# Rectifier-SinglePhase-FullControlled-TCA.net
KiCad netlist of a schematic drawn in Altium Designer
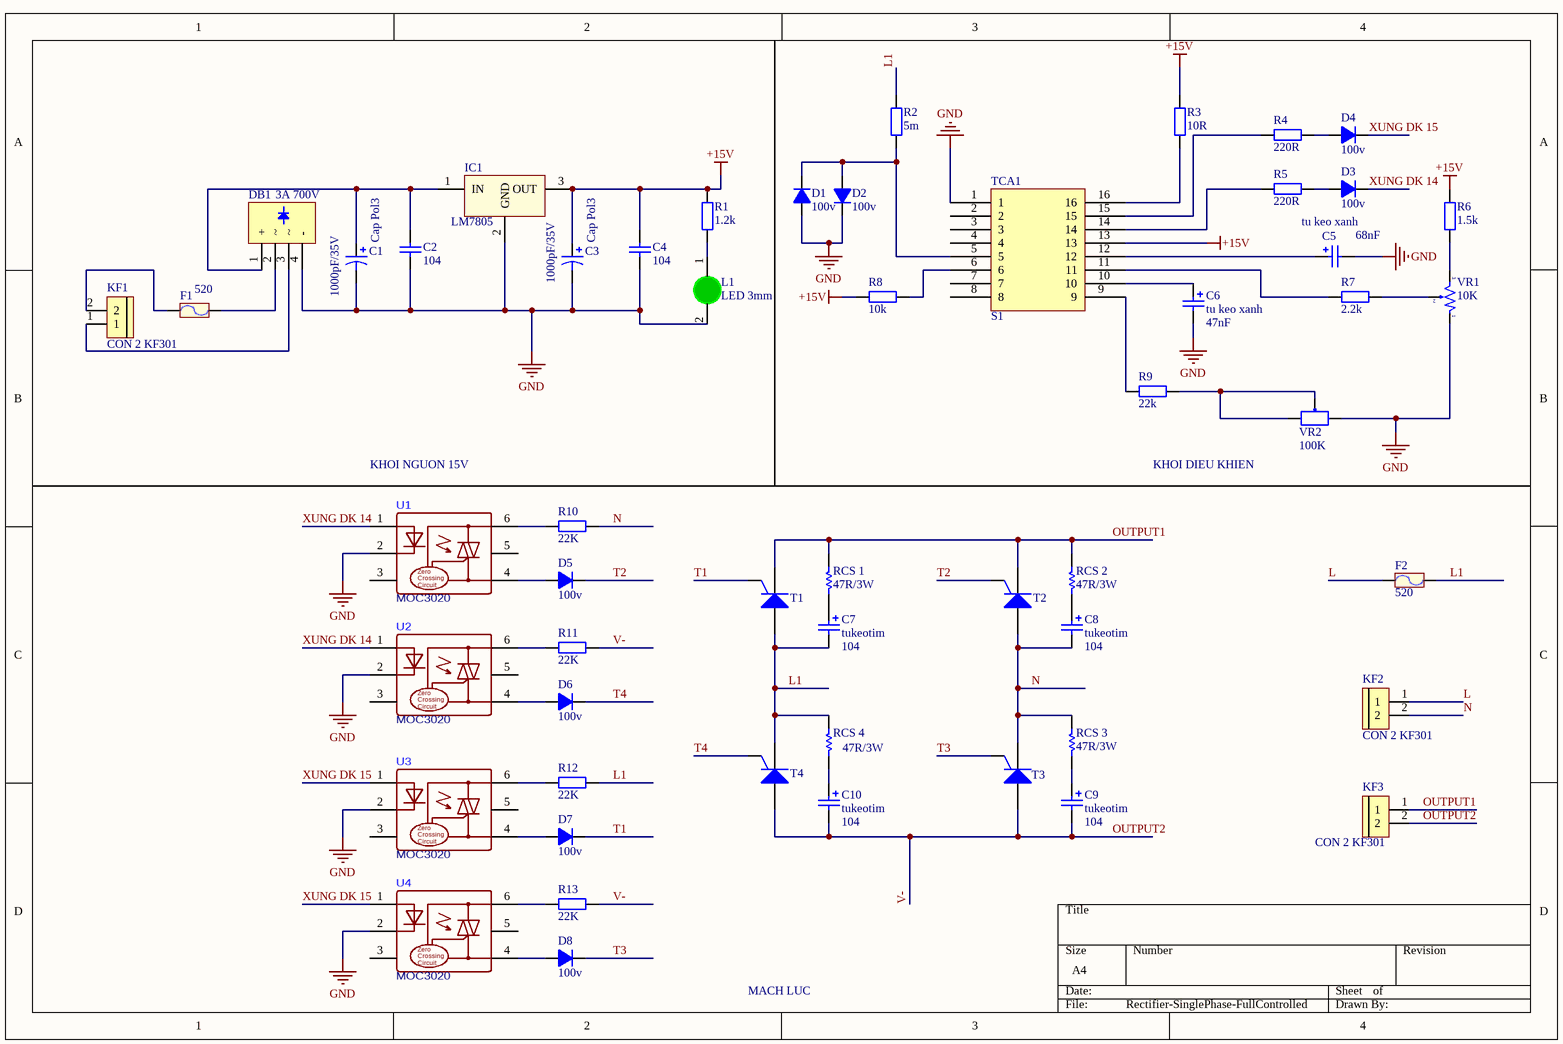
[diagram p0: Rectifier-SinglePhase-FullControlled-TCA785.SchDoc]

(export (version "E")
  (design (tool "Eeschema 10.0.6"))
  (components
    (comp (ref "C1")
      (value "Cap Pol3")
      (footprint "CP2/5")
      (description "Polarized Capacitor (Surface Mount)")
      (fields (field (name "ALTIUM_VALUE") "1000pF/35V") (field (name "PUBLISHER") "Altium Limited"))
      (libsource (lib "syhaunguyen") (part "Cap Pol3_3"))
    )
    (comp (ref "C2")
      (value "104")
      (footprint "tu gom")
      (description "Cắm")
      (libsource (lib "Tu dien") (part "Tu gom 104 50V"))
    )
    (comp (ref "C3")
      (value "Cap Pol3")
      (footprint "CP2/5")
      (description "Polarized Capacitor (Surface Mount)")
      (fields (field (name "ALTIUM_VALUE") "1000pF/35V") (field (name "PUBLISHER") "Altium Limited"))
      (libsource (lib "syhaunguyen") (part "Cap Pol3_3"))
    )
    (comp (ref "C4")
      (value "104")
      (footprint "tu gom")
      (description "Cắm")
      (libsource (lib "Tu dien") (part "Tu gom 104 50V"))
    )
    (comp (ref "C5")
      (value "tu keo xanh")
      (footprint "tu keo xanh")
      (description "Polarized Capacitor (Surface Mount)")
      (fields (field (name "ALTIUM_VALUE") "68nF") (field (name "PUBLISHER") "Altium Limited"))
      (libsource (lib "syhaunguyen") (part "tu keo xanh"))
    )
    (comp (ref "C6")
      (value "tu keo xanh")
      (footprint "tu keo xanh")
      (description "Polarized Capacitor (Surface Mount)")
      (fields (field (name "ALTIUM_VALUE") "47nF") (field (name "PUBLISHER") "Altium Limited"))
      (libsource (lib "syhaunguyen") (part "tu keo xanh"))
    )
    (comp (ref "C7")
      (value "tukeotim")
      (footprint "tu keo")
      (description "Polarized Capacitor (Surface Mount)")
      (fields (field (name "ALTIUM_VALUE") "104") (field (name "PUBLISHER") "Altium Limited"))
      (libsource (lib "syhaunguyen") (part "tu keo tim"))
    )
    (comp (ref "C8")
      (value "tukeotim")
      (footprint "tu keo")
      (description "Polarized Capacitor (Surface Mount)")
      (fields (field (name "ALTIUM_VALUE") "104") (field (name "PUBLISHER") "Altium Limited"))
      (libsource (lib "syhaunguyen") (part "tu keo tim"))
    )
    (comp (ref "C9")
      (value "tukeotim")
      (footprint "tu keo")
      (description "Polarized Capacitor (Surface Mount)")
      (fields (field (name "ALTIUM_VALUE") "104") (field (name "PUBLISHER") "Altium Limited"))
      (libsource (lib "syhaunguyen") (part "tu keo tim"))
    )
    (comp (ref "C10")
      (value "tukeotim")
      (footprint "tu keo")
      (description "Polarized Capacitor (Surface Mount)")
      (fields (field (name "ALTIUM_VALUE") "104") (field (name "PUBLISHER") "Altium Limited"))
      (libsource (lib "syhaunguyen") (part "tu keo tim"))
    )
    (comp (ref "D1")
      (value "100v")
      (footprint "DIODE 1A")
      (description "Cắm")
      (libsource (lib "Altium_Lib_by_KhueNguyenCreator") (part "Diode 1N4007"))
    )
    (comp (ref "D2")
      (value "100v")
      (footprint "DIODE 1A")
      (description "Cắm")
      (libsource (lib "Altium_Lib_by_KhueNguyenCreator") (part "Diode 1N4007"))
    )
    (comp (ref "D3")
      (value "100v")
      (footprint "DIODE 1A")
      (description "Cắm")
      (libsource (lib "Altium_Lib_by_KhueNguyenCreator") (part "Diode 1N4007"))
    )
    (comp (ref "D4")
      (value "100v")
      (footprint "DIODE 1A")
      (description "Cắm")
      (libsource (lib "Altium_Lib_by_KhueNguyenCreator") (part "Diode 1N4007"))
    )
    (comp (ref "D5")
      (value "100v")
      (footprint "DIODE 1A")
      (description "Cắm")
      (libsource (lib "Altium_Lib_by_KhueNguyenCreator") (part "Diode 1N4007"))
    )
    (comp (ref "D6")
      (value "100v")
      (footprint "DIODE 1A")
      (description "Cắm")
      (libsource (lib "Altium_Lib_by_KhueNguyenCreator") (part "Diode 1N4007"))
    )
    (comp (ref "D7")
      (value "100v")
      (footprint "DIODE 1A")
      (description "Cắm")
      (libsource (lib "Altium_Lib_by_KhueNguyenCreator") (part "Diode 1N4007"))
    )
    (comp (ref "D8")
      (value "100v")
      (footprint "DIODE 1A")
      (description "Cắm")
      (libsource (lib "Altium_Lib_by_KhueNguyenCreator") (part "Diode 1N4007"))
    )
    (comp (ref "DB1")
      (value "3A 700V")
      (footprint "DIODE CAU 2A 3A CAM")
      (description "Cắm")
      (libsource (lib "Altium_Lib_by_KhueNguyenCreator") (part "Diode CAU 3A"))
    )
    (comp (ref "F1")
      (value "520")
      (footprint "De Cau Chi 520 630")
      (description "5x20mm")
      (libsource (lib "Altium_Lib_by_KhueNguyenCreator") (part "De Cau Chi 520 630"))
    )
    (comp (ref "F2")
      (value "520")
      (footprint "De Cau Chi 520 630")
      (description "5x20mm")
      (libsource (lib "Altium_Lib_by_KhueNguyenCreator") (part "De Cau Chi 520 630"))
    )
    (comp (ref "IC1")
      (value "LM7805")
      (footprint "QTO-220")
      (description "On ap +, from + 5 to + 24VDC")
      (libsource (lib "Free Documents") (part "LM78xx"))
    )
    (comp (ref "KF1")
      (value "CON 2 KF301")
      (footprint "Con 2 KF301 5.08")
      (description "Cắm")
      (libsource (lib "") (part "CON 2 KF301_1"))
    )
    (comp (ref "KF2")
      (value "CON 2 KF301")
      (footprint "Con 2 KF301 5.08")
      (description "Cắm")
      (libsource (lib "Altium_Lib_by_KhueNguyenCreator") (part "CON 2 KF301"))
    )
    (comp (ref "KF3")
      (value "CON 2 KF301")
      (footprint "Con 2 KF301 5.08")
      (description "Cắm")
      (libsource (lib "Altium_Lib_by_KhueNguyenCreator") (part "CON 2 KF301"))
    )
    (comp (ref "L1")
      (value "LED 3mm")
      (footprint "LED-3MM-GREEN")
      (description "Cắm")
      (libsource (lib "Altium_Lib_by_KhueNguyenCreator") (part "LED 3mm Xanh La"))
    )
    (comp (ref "R1")
      (value "1.2k")
      (footprint "tro vach 1/4w")
      (description "Cắm")
      (libsource (lib "Altium_Lib_by_KhueNguyenCreator") (part "Tro Vach 1/4W 5% 1.2R"))
    )
    (comp (ref "R2")
      (value "5m")
      (footprint "tro vach 1/4w")
      (description "Cắm")
      (libsource (lib "Altium_Lib_by_KhueNguyenCreator") (part "Tro Vach 1/4W 5% 1.2R"))
    )
    (comp (ref "R3")
      (value "10R")
      (footprint "tro vach 1/4w")
      (description "Cắm")
      (libsource (lib "Altium_Lib_by_KhueNguyenCreator") (part "Tro Vach 1/4W 5% 1.2R"))
    )
    (comp (ref "R4")
      (value "220R")
      (footprint "tro vach 1/4w")
      (description "Cắm")
      (libsource (lib "Altium_Lib_by_KhueNguyenCreator") (part "Tro Vach 1/4W 5% 1.2R"))
    )
    (comp (ref "R5")
      (value "220R")
      (footprint "tro vach 1/4w")
      (description "Cắm")
      (libsource (lib "Altium_Lib_by_KhueNguyenCreator") (part "Tro Vach 1/4W 5% 1.2R"))
    )
    (comp (ref "R6")
      (value "1.5k")
      (footprint "tro vach 1/4w")
      (description "Cắm")
      (libsource (lib "Altium_Lib_by_KhueNguyenCreator") (part "Tro Vach 1/4W 5% 1.2R"))
    )
    (comp (ref "R7")
      (value "2.2k")
      (footprint "tro vach 1/4w")
      (description "Cắm")
      (libsource (lib "Altium_Lib_by_KhueNguyenCreator") (part "Tro Vach 1/4W 5% 1.2R"))
    )
    (comp (ref "R8")
      (value "10k")
      (footprint "tro vach 1/4w")
      (description "Cắm")
      (libsource (lib "Altium_Lib_by_KhueNguyenCreator") (part "Tro Vach 1/4W 5% 1.2R"))
    )
    (comp (ref "R9")
      (value "22k")
      (footprint "tro vach 1/4w")
      (description "Cắm")
      (libsource (lib "Altium_Lib_by_KhueNguyenCreator") (part "Tro Vach 1/4W 5% 1.2R"))
    )
    (comp (ref "R10")
      (value "22K")
      (footprint "tro vach 1/4w")
      (description "Cắm")
      (libsource (lib "Altium_Lib_by_KhueNguyenCreator") (part "Tro Vach 1/4W 5% 1.2R"))
    )
    (comp (ref "R11")
      (value "22K")
      (footprint "tro vach 1/4w")
      (description "Cắm")
      (libsource (lib "Altium_Lib_by_KhueNguyenCreator") (part "Tro Vach 1/4W 5% 1.2R"))
    )
    (comp (ref "R12")
      (value "22K")
      (footprint "tro vach 1/4w")
      (description "Cắm")
      (libsource (lib "Altium_Lib_by_KhueNguyenCreator") (part "Tro Vach 1/4W 5% 1.2R"))
    )
    (comp (ref "R13")
      (value "22K")
      (footprint "tro vach 1/4w")
      (description "Cắm")
      (libsource (lib "Altium_Lib_by_KhueNguyenCreator") (part "Tro Vach 1/4W 5% 1.2R"))
    )
    (comp (ref "RCS 1")
      (value "47R/3W")
      (footprint "TRO CONG SUAT")
      (description "Resistor")
      (fields
        (field (name "MANUFACTURER") "Generic Components")
        (field (name "Comment") "Res")
        (field (name "PUBLISHER") "Altium Hobart Technology Centre")
      )
      (libsource (lib "syhaunguyen") (part "TRO CONG SUAT"))
    )
    (comp (ref "RCS 2")
      (value "47R/3W")
      (footprint "TRO CONG SUAT")
      (description "Resistor")
      (fields
        (field (name "MANUFACTURER") "Generic Components")
        (field (name "Comment") "Res")
        (field (name "PUBLISHER") "Altium Hobart Technology Centre")
      )
      (libsource (lib "syhaunguyen") (part "TRO CONG SUAT"))
    )
    (comp (ref "RCS 3")
      (value "47R/3W")
      (footprint "TRO CONG SUAT")
      (description "Resistor")
      (fields
        (field (name "MANUFACTURER") "Generic Components")
        (field (name "Comment") "Res")
        (field (name "PUBLISHER") "Altium Hobart Technology Centre")
      )
      (libsource (lib "syhaunguyen") (part "TRO CONG SUAT"))
    )
    (comp (ref "RCS 4")
      (value "47R/3W")
      (footprint "TRO CONG SUAT")
      (description "Resistor")
      (fields
        (field (name "MANUFACTURER") "Generic Components")
        (field (name "Comment") "Res")
        (field (name "PUBLISHER") "Altium Hobart Technology Centre")
      )
      (libsource (lib "syhaunguyen") (part "TRO CONG SUAT"))
    )
    (comp (ref "T1")
      (value "SCR Thyristror")
      (footprint "scr")
      (libsource (lib "syhaunguyen") (part "SCR_1"))
    )
    (comp (ref "T2")
      (value "SCR Thyristror")
      (footprint "scr")
      (libsource (lib "syhaunguyen") (part "SCR_1"))
    )
    (comp (ref "T3")
      (value "SCR Thyristror")
      (footprint "scr")
      (libsource (lib "syhaunguyen") (part "SCR_1"))
    )
    (comp (ref "T4")
      (value "SCR Thyristror")
      (footprint "scr")
      (libsource (lib "syhaunguyen") (part "SCR_1"))
    )
    (comp (ref "TCA1")
      (value "S1")
      (footprint "DIP16/W0.3 - duplicate")
      (libsource (lib "syhaunguyen") (part "TCA 785"))
    )
    (comp (ref "U1")
      (value "MOC3020")
      (footprint "DIP6")
      (libsource (lib "Altium_Lib_by_KhueNguyenCreator") (part "MOC3063M"))
    )
    (comp (ref "U2")
      (value "MOC3020")
      (footprint "DIP6")
      (libsource (lib "Altium_Lib_by_KhueNguyenCreator") (part "MOC3063M"))
    )
    (comp (ref "U3")
      (value "MOC3020")
      (footprint "DIP6")
      (libsource (lib "Altium_Lib_by_KhueNguyenCreator") (part "MOC3063M"))
    )
    (comp (ref "U4")
      (value "MOC3020")
      (footprint "DIP6")
      (libsource (lib "Altium_Lib_by_KhueNguyenCreator") (part "MOC3063M"))
    )
    (comp (ref "VR1")
      (value "10K")
      (footprint "Bien Tro Volume Don")
      (description "Cắm")
      (libsource (lib "Dien Tro") (part "Triet Ap Don 5k"))
    )
    (comp (ref "VR2")
      (value "100K")
      (footprint "Bien Tro Vi Chinh Dung")
      (description "Cắm")
      (libsource (lib "Altium_Lib_by_KhueNguyenCreator") (part "Bien Tro Tinh Chinh 100R Dung"))
    )
  )
  (nets
    (net (code "1") (name "+15V") (class "Default")
      (node (ref "C3") (pin "1") (pinfunction "1_1") (pintype "passive"))
      (node (ref "C4") (pin "1") (pinfunction "1_1") (pintype "passive"))
      (node (ref "IC1") (pin "3") (pinfunction "OUT_3") (pintype "passive"))
      (node (ref "R1") (pin "2") (pinfunction "2_2") (pintype "passive"))
      (node (ref "R3") (pin "2") (pinfunction "2_2") (pintype "passive"))
      (node (ref "R6") (pin "1") (pinfunction "1_1") (pintype "passive"))
      (node (ref "R8") (pin "2") (pinfunction "2_2") (pintype "passive"))
      (node (ref "TCA1") (pin "13") (pinfunction "13_13") (pintype "passive"))
    )
    (net (code "2") (name "/L") (class "Default")
      (node (ref "F2") (pin "1") (pinfunction "1_1") (pintype "passive"))
      (node (ref "KF2") (pin "1") (pinfunction "1_1") (pintype "passive"))
    )
    (net (code "3") (name "/L1") (class "Default")
      (node (ref "C7") (pin "2") (pinfunction "2_2") (pintype "passive"))
      (node (ref "F2") (pin "2") (pinfunction "2_2") (pintype "passive"))
      (node (ref "R12") (pin "1") (pinfunction "1_1") (pintype "passive"))
      (node (ref "R2") (pin "2") (pinfunction "2_2") (pintype "passive"))
      (node (ref "RCS 4") (pin "2") (pinfunction "2_2") (pintype "passive"))
      (node (ref "T1") (pin "2") (pinfunction "A_2") (pintype "passive"))
      (node (ref "T4") (pin "1") (pinfunction "K_1") (pintype "passive"))
    )
    (net (code "4") (name "/N") (class "Default")
      (node (ref "C8") (pin "2") (pinfunction "2_2") (pintype "passive"))
      (node (ref "KF2") (pin "2") (pinfunction "2_2") (pintype "passive"))
      (node (ref "R10") (pin "1") (pinfunction "1_1") (pintype "passive"))
      (node (ref "RCS 3") (pin "2") (pinfunction "2_2") (pintype "passive"))
      (node (ref "T2") (pin "2") (pinfunction "A_2") (pintype "passive"))
      (node (ref "T3") (pin "1") (pinfunction "K_1") (pintype "passive"))
    )
    (net (code "5") (name "/OUTPUT1") (class "Default")
      (node (ref "KF3") (pin "1") (pinfunction "1_1") (pintype "passive"))
      (node (ref "RCS 1") (pin "2") (pinfunction "2_2") (pintype "passive"))
      (node (ref "RCS 2") (pin "2") (pinfunction "2_2") (pintype "passive"))
      (node (ref "T1") (pin "1") (pinfunction "K_1") (pintype "passive"))
      (node (ref "T2") (pin "1") (pinfunction "K_1") (pintype "passive"))
    )
    (net (code "6") (name "/OUTPUT2") (class "Default")
      (node (ref "C10") (pin "2") (pinfunction "2_2") (pintype "passive"))
      (node (ref "C9") (pin "2") (pinfunction "2_2") (pintype "passive"))
      (node (ref "KF3") (pin "2") (pinfunction "2_2") (pintype "passive"))
      (node (ref "R11") (pin "1") (pinfunction "1_1") (pintype "passive"))
      (node (ref "R13") (pin "1") (pinfunction "1_1") (pintype "passive"))
      (node (ref "T3") (pin "2") (pinfunction "A_2") (pintype "passive"))
      (node (ref "T4") (pin "2") (pinfunction "A_2") (pintype "passive"))
    )
    (net (code "7") (name "/T1") (class "Default")
      (node (ref "D7") (pin "2") (pinfunction "K_2") (pintype "passive"))
      (node (ref "T1") (pin "3") (pinfunction "G_3") (pintype "passive"))
    )
    (net (code "8") (name "/T2") (class "Default")
      (node (ref "D5") (pin "2") (pinfunction "K_2") (pintype "passive"))
      (node (ref "T2") (pin "3") (pinfunction "G_3") (pintype "passive"))
    )
    (net (code "9") (name "/T3") (class "Default")
      (node (ref "D8") (pin "2") (pinfunction "K_2") (pintype "passive"))
      (node (ref "T3") (pin "3") (pinfunction "G_3") (pintype "passive"))
    )
    (net (code "10") (name "/T4") (class "Default")
      (node (ref "D6") (pin "2") (pinfunction "K_2") (pintype "passive"))
      (node (ref "T4") (pin "3") (pinfunction "G_3") (pintype "passive"))
    )
    (net (code "11") (name "/XUNG DK 14") (class "Default")
      (node (ref "D3") (pin "2") (pinfunction "K_2") (pintype "passive"))
      (node (ref "U1") (pin "1") (pinfunction "A_1") (pintype "passive"))
      (node (ref "U2") (pin "1") (pinfunction "A_1") (pintype "passive"))
    )
    (net (code "12") (name "/XUNG DK 15") (class "Default")
      (node (ref "D4") (pin "2") (pinfunction "K_2") (pintype "passive"))
      (node (ref "U3") (pin "1") (pinfunction "A_1") (pintype "passive"))
      (node (ref "U4") (pin "1") (pinfunction "A_1") (pintype "passive"))
    )
    (net (code "13") (name "GND") (class "Default")
      (node (ref "C1") (pin "2") (pinfunction "2_2") (pintype "passive"))
      (node (ref "C2") (pin "2") (pinfunction "2_2") (pintype "passive"))
      (node (ref "C3") (pin "2") (pinfunction "2_2") (pintype "passive"))
      (node (ref "C4") (pin "2") (pinfunction "2_2") (pintype "passive"))
      (node (ref "C5") (pin "2") (pinfunction "2_2") (pintype "passive"))
      (node (ref "C6") (pin "2") (pinfunction "2_2") (pintype "passive"))
      (node (ref "D1") (pin "1") (pinfunction "A_1") (pintype "passive"))
      (node (ref "D2") (pin "2") (pinfunction "K_2") (pintype "passive"))
      (node (ref "DB1") (pin "4") (pinfunction "-_4") (pintype "passive"))
      (node (ref "IC1") (pin "2") (pinfunction "GND_2") (pintype "passive"))
      (node (ref "L1") (pin "2") (pinfunction "K_2") (pintype "passive"))
      (node (ref "TCA1") (pin "1") (pinfunction "1_1") (pintype "passive"))
      (node (ref "U1") (pin "2") (pinfunction "K_2") (pintype "passive"))
      (node (ref "U2") (pin "2") (pinfunction "K_2") (pintype "passive"))
      (node (ref "U3") (pin "2") (pinfunction "K_2") (pintype "passive"))
      (node (ref "U4") (pin "2") (pinfunction "K_2") (pintype "passive"))
      (node (ref "VR1") (pin "1") (pinfunction "1_1") (pintype "passive"))
      (node (ref "VR2") (pin "3") (pinfunction "3_3") (pintype "passive"))
    )
    (net (code "14") (name "Net-(C5-Pad1)") (class "Default")
      (node (ref "C5") (pin "1") (pinfunction "1_1") (pintype "passive"))
      (node (ref "TCA1") (pin "12") (pinfunction "12_12") (pintype "passive"))
    )
    (net (code "15") (name "Net-(C6-Pad1)") (class "Default")
      (node (ref "C6") (pin "1") (pinfunction "1_1") (pintype "passive"))
      (node (ref "TCA1") (pin "10") (pinfunction "10_10") (pintype "passive"))
    )
    (net (code "16") (name "Net-(C7-Pad1)") (class "Default")
      (node (ref "C7") (pin "1") (pinfunction "1_1") (pintype "passive"))
      (node (ref "RCS 1") (pin "1") (pinfunction "1_1") (pintype "passive"))
    )
    (net (code "17") (name "Net-(C8-Pad1)") (class "Default")
      (node (ref "C8") (pin "1") (pinfunction "1_1") (pintype "passive"))
      (node (ref "RCS 2") (pin "1") (pinfunction "1_1") (pintype "passive"))
    )
    (net (code "18") (name "Net-(C9-Pad1)") (class "Default")
      (node (ref "C9") (pin "1") (pinfunction "1_1") (pintype "passive"))
      (node (ref "RCS 3") (pin "1") (pinfunction "1_1") (pintype "passive"))
    )
    (net (code "19") (name "Net-(C10-Pad1)") (class "Default")
      (node (ref "C10") (pin "1") (pinfunction "1_1") (pintype "passive"))
      (node (ref "RCS 4") (pin "1") (pinfunction "1_1") (pintype "passive"))
    )
    (net (code "20") (name "Net-(D1-K)") (class "Default")
      (node (ref "D1") (pin "2") (pinfunction "K_2") (pintype "passive"))
      (node (ref "D2") (pin "1") (pinfunction "A_1") (pintype "passive"))
      (node (ref "R2") (pin "1") (pinfunction "1_1") (pintype "passive"))
      (node (ref "TCA1") (pin "5") (pinfunction "5_5") (pintype "passive"))
    )
    (net (code "21") (name "Net-(D3-A)") (class "Default")
      (node (ref "D3") (pin "1") (pinfunction "A_1") (pintype "passive"))
      (node (ref "R5") (pin "1") (pinfunction "1_1") (pintype "passive"))
    )
    (net (code "22") (name "Net-(D4-A)") (class "Default")
      (node (ref "D4") (pin "1") (pinfunction "A_1") (pintype "passive"))
      (node (ref "R4") (pin "1") (pinfunction "1_1") (pintype "passive"))
    )
    (net (code "23") (name "Net-(D5-A)") (class "Default")
      (node (ref "D5") (pin "1") (pinfunction "A_1") (pintype "passive"))
      (node (ref "U1") (pin "4") (pinfunction "MT_4") (pintype "passive"))
    )
    (net (code "24") (name "Net-(D6-A)") (class "Default")
      (node (ref "D6") (pin "1") (pinfunction "A_1") (pintype "passive"))
      (node (ref "U2") (pin "4") (pinfunction "MT_4") (pintype "passive"))
    )
    (net (code "25") (name "Net-(D7-A)") (class "Default")
      (node (ref "D7") (pin "1") (pinfunction "A_1") (pintype "passive"))
      (node (ref "U3") (pin "4") (pinfunction "MT_4") (pintype "passive"))
    )
    (net (code "26") (name "Net-(D8-A)") (class "Default")
      (node (ref "D8") (pin "1") (pinfunction "A_1") (pintype "passive"))
      (node (ref "U4") (pin "4") (pinfunction "MT_4") (pintype "passive"))
    )
    (net (code "27") (name "Net-(DB1-+)") (class "Default")
      (node (ref "C1") (pin "1") (pinfunction "1_1") (pintype "passive"))
      (node (ref "C2") (pin "1") (pinfunction "1_1") (pintype "passive"))
      (node (ref "DB1") (pin "1") (pinfunction "+_1") (pintype "passive"))
      (node (ref "IC1") (pin "1") (pinfunction "IN_1") (pintype "passive"))
    )
    (net (code "28") (name "Net-(DB1-~-Pad2)") (class "Default")
      (node (ref "DB1") (pin "2") (pinfunction "~_2") (pintype "passive"))
      (node (ref "F1") (pin "2") (pinfunction "2_2") (pintype "passive"))
    )
    (net (code "29") (name "Net-(DB1-~-Pad3)") (class "Default")
      (node (ref "DB1") (pin "3") (pinfunction "~_3") (pintype "passive"))
      (node (ref "KF1") (pin "1") (pinfunction "1_1") (pintype "passive"))
    )
    (net (code "30") (name "Net-(F1-Pad1)") (class "Default")
      (node (ref "F1") (pin "1") (pinfunction "1_1") (pintype "passive"))
      (node (ref "KF1") (pin "2") (pinfunction "2_2") (pintype "passive"))
    )
    (net (code "31") (name "Net-(L1-A)") (class "Default")
      (node (ref "L1") (pin "1") (pinfunction "A_1") (pintype "passive"))
      (node (ref "R1") (pin "1") (pinfunction "1_1") (pintype "passive"))
    )
    (net (code "32") (name "Net-(R3-Pad1)") (class "Default")
      (node (ref "R3") (pin "1") (pinfunction "1_1") (pintype "passive"))
      (node (ref "TCA1") (pin "16") (pinfunction "16_16") (pintype "passive"))
    )
    (net (code "33") (name "Net-(R4-Pad2)") (class "Default")
      (node (ref "R4") (pin "2") (pinfunction "2_2") (pintype "passive"))
      (node (ref "TCA1") (pin "15") (pinfunction "15_15") (pintype "passive"))
    )
    (net (code "34") (name "Net-(R5-Pad2)") (class "Default")
      (node (ref "R5") (pin "2") (pinfunction "2_2") (pintype "passive"))
      (node (ref "TCA1") (pin "14") (pinfunction "14_14") (pintype "passive"))
    )
    (net (code "35") (name "Net-(R6-Pad2)") (class "Default")
      (node (ref "R6") (pin "2") (pinfunction "2_2") (pintype "passive"))
      (node (ref "VR1") (pin "3") (pinfunction "3_3") (pintype "passive"))
    )
    (net (code "36") (name "Net-(R7-Pad1)") (class "Default")
      (node (ref "R7") (pin "1") (pinfunction "1_1") (pintype "passive"))
      (node (ref "VR1") (pin "2") (pinfunction "2_2") (pintype "passive"))
    )
    (net (code "37") (name "Net-(R7-Pad2)") (class "Default")
      (node (ref "R7") (pin "2") (pinfunction "2_2") (pintype "passive"))
      (node (ref "TCA1") (pin "11") (pinfunction "11_11") (pintype "passive"))
    )
    (net (code "38") (name "Net-(R8-Pad1)") (class "Default")
      (node (ref "R8") (pin "1") (pinfunction "1_1") (pintype "passive"))
      (node (ref "TCA1") (pin "6") (pinfunction "6_6") (pintype "passive"))
    )
    (net (code "39") (name "Net-(R9-Pad1)") (class "Default")
      (node (ref "R9") (pin "1") (pinfunction "1_1") (pintype "passive"))
      (node (ref "VR2") (pin "1") (pinfunction "1_1") (pintype "passive"))
      (node (ref "VR2") (pin "2") (pinfunction "2_2") (pintype "passive"))
    )
    (net (code "40") (name "Net-(R9-Pad2)") (class "Default")
      (node (ref "R9") (pin "2") (pinfunction "2_2") (pintype "passive"))
      (node (ref "TCA1") (pin "9") (pinfunction "9_9") (pintype "passive"))
    )
    (net (code "41") (name "Net-(R10-Pad2)") (class "Default")
      (node (ref "R10") (pin "2") (pinfunction "2_2") (pintype "passive"))
      (node (ref "U1") (pin "6") (pinfunction "MT_6") (pintype "passive"))
    )
    (net (code "42") (name "Net-(R11-Pad2)") (class "Default")
      (node (ref "R11") (pin "2") (pinfunction "2_2") (pintype "passive"))
      (node (ref "U2") (pin "6") (pinfunction "MT_6") (pintype "passive"))
    )
    (net (code "43") (name "Net-(R12-Pad2)") (class "Default")
      (node (ref "R12") (pin "2") (pinfunction "2_2") (pintype "passive"))
      (node (ref "U3") (pin "6") (pinfunction "MT_6") (pintype "passive"))
    )
    (net (code "44") (name "Net-(R13-Pad2)") (class "Default")
      (node (ref "R13") (pin "2") (pinfunction "2_2") (pintype "passive"))
      (node (ref "U4") (pin "6") (pinfunction "MT_6") (pintype "passive"))
    )
    (net (code "45") (name "unconnected-(TCA1-Pad2)") (class "Default")
      (node (ref "TCA1") (pin "2") (pinfunction "2_2") (pintype "passive"))
    )
    (net (code "46") (name "unconnected-(TCA1-Pad3)") (class "Default")
      (node (ref "TCA1") (pin "3") (pinfunction "3_3") (pintype "passive"))
    )
    (net (code "47") (name "unconnected-(TCA1-Pad4)") (class "Default")
      (node (ref "TCA1") (pin "4") (pinfunction "4_4") (pintype "passive"))
    )
    (net (code "48") (name "unconnected-(TCA1-Pad7)") (class "Default")
      (node (ref "TCA1") (pin "7") (pinfunction "7_7") (pintype "passive"))
    )
    (net (code "49") (name "unconnected-(TCA1-Pad8)") (class "Default")
      (node (ref "TCA1") (pin "8") (pinfunction "8_8") (pintype "passive"))
    )
    (net (code "50") (name "unconnected-(U1-NC-Pad3)") (class "Default")
      (node (ref "U1") (pin "3") (pinfunction "NC_3") (pintype "passive"))
    )
    (net (code "51") (name "unconnected-(U1-NC-Pad5)") (class "Default")
      (node (ref "U1") (pin "5") (pinfunction "NC_5") (pintype "passive"))
    )
    (net (code "52") (name "unconnected-(U2-NC-Pad3)") (class "Default")
      (node (ref "U2") (pin "3") (pinfunction "NC_3") (pintype "passive"))
    )
    (net (code "53") (name "unconnected-(U2-NC-Pad5)") (class "Default")
      (node (ref "U2") (pin "5") (pinfunction "NC_5") (pintype "passive"))
    )
    (net (code "54") (name "unconnected-(U3-NC-Pad3)") (class "Default")
      (node (ref "U3") (pin "3") (pinfunction "NC_3") (pintype "passive"))
    )
    (net (code "55") (name "unconnected-(U3-NC-Pad5)") (class "Default")
      (node (ref "U3") (pin "5") (pinfunction "NC_5") (pintype "passive"))
    )
    (net (code "56") (name "unconnected-(U4-NC-Pad3)") (class "Default")
      (node (ref "U4") (pin "3") (pinfunction "NC_3") (pintype "passive"))
    )
    (net (code "57") (name "unconnected-(U4-NC-Pad5)") (class "Default")
      (node (ref "U4") (pin "5") (pinfunction "NC_5") (pintype "passive"))
    )
  )
)
